# Regulation.net
KiCad netlist of a schematic drawn in Altium Designer
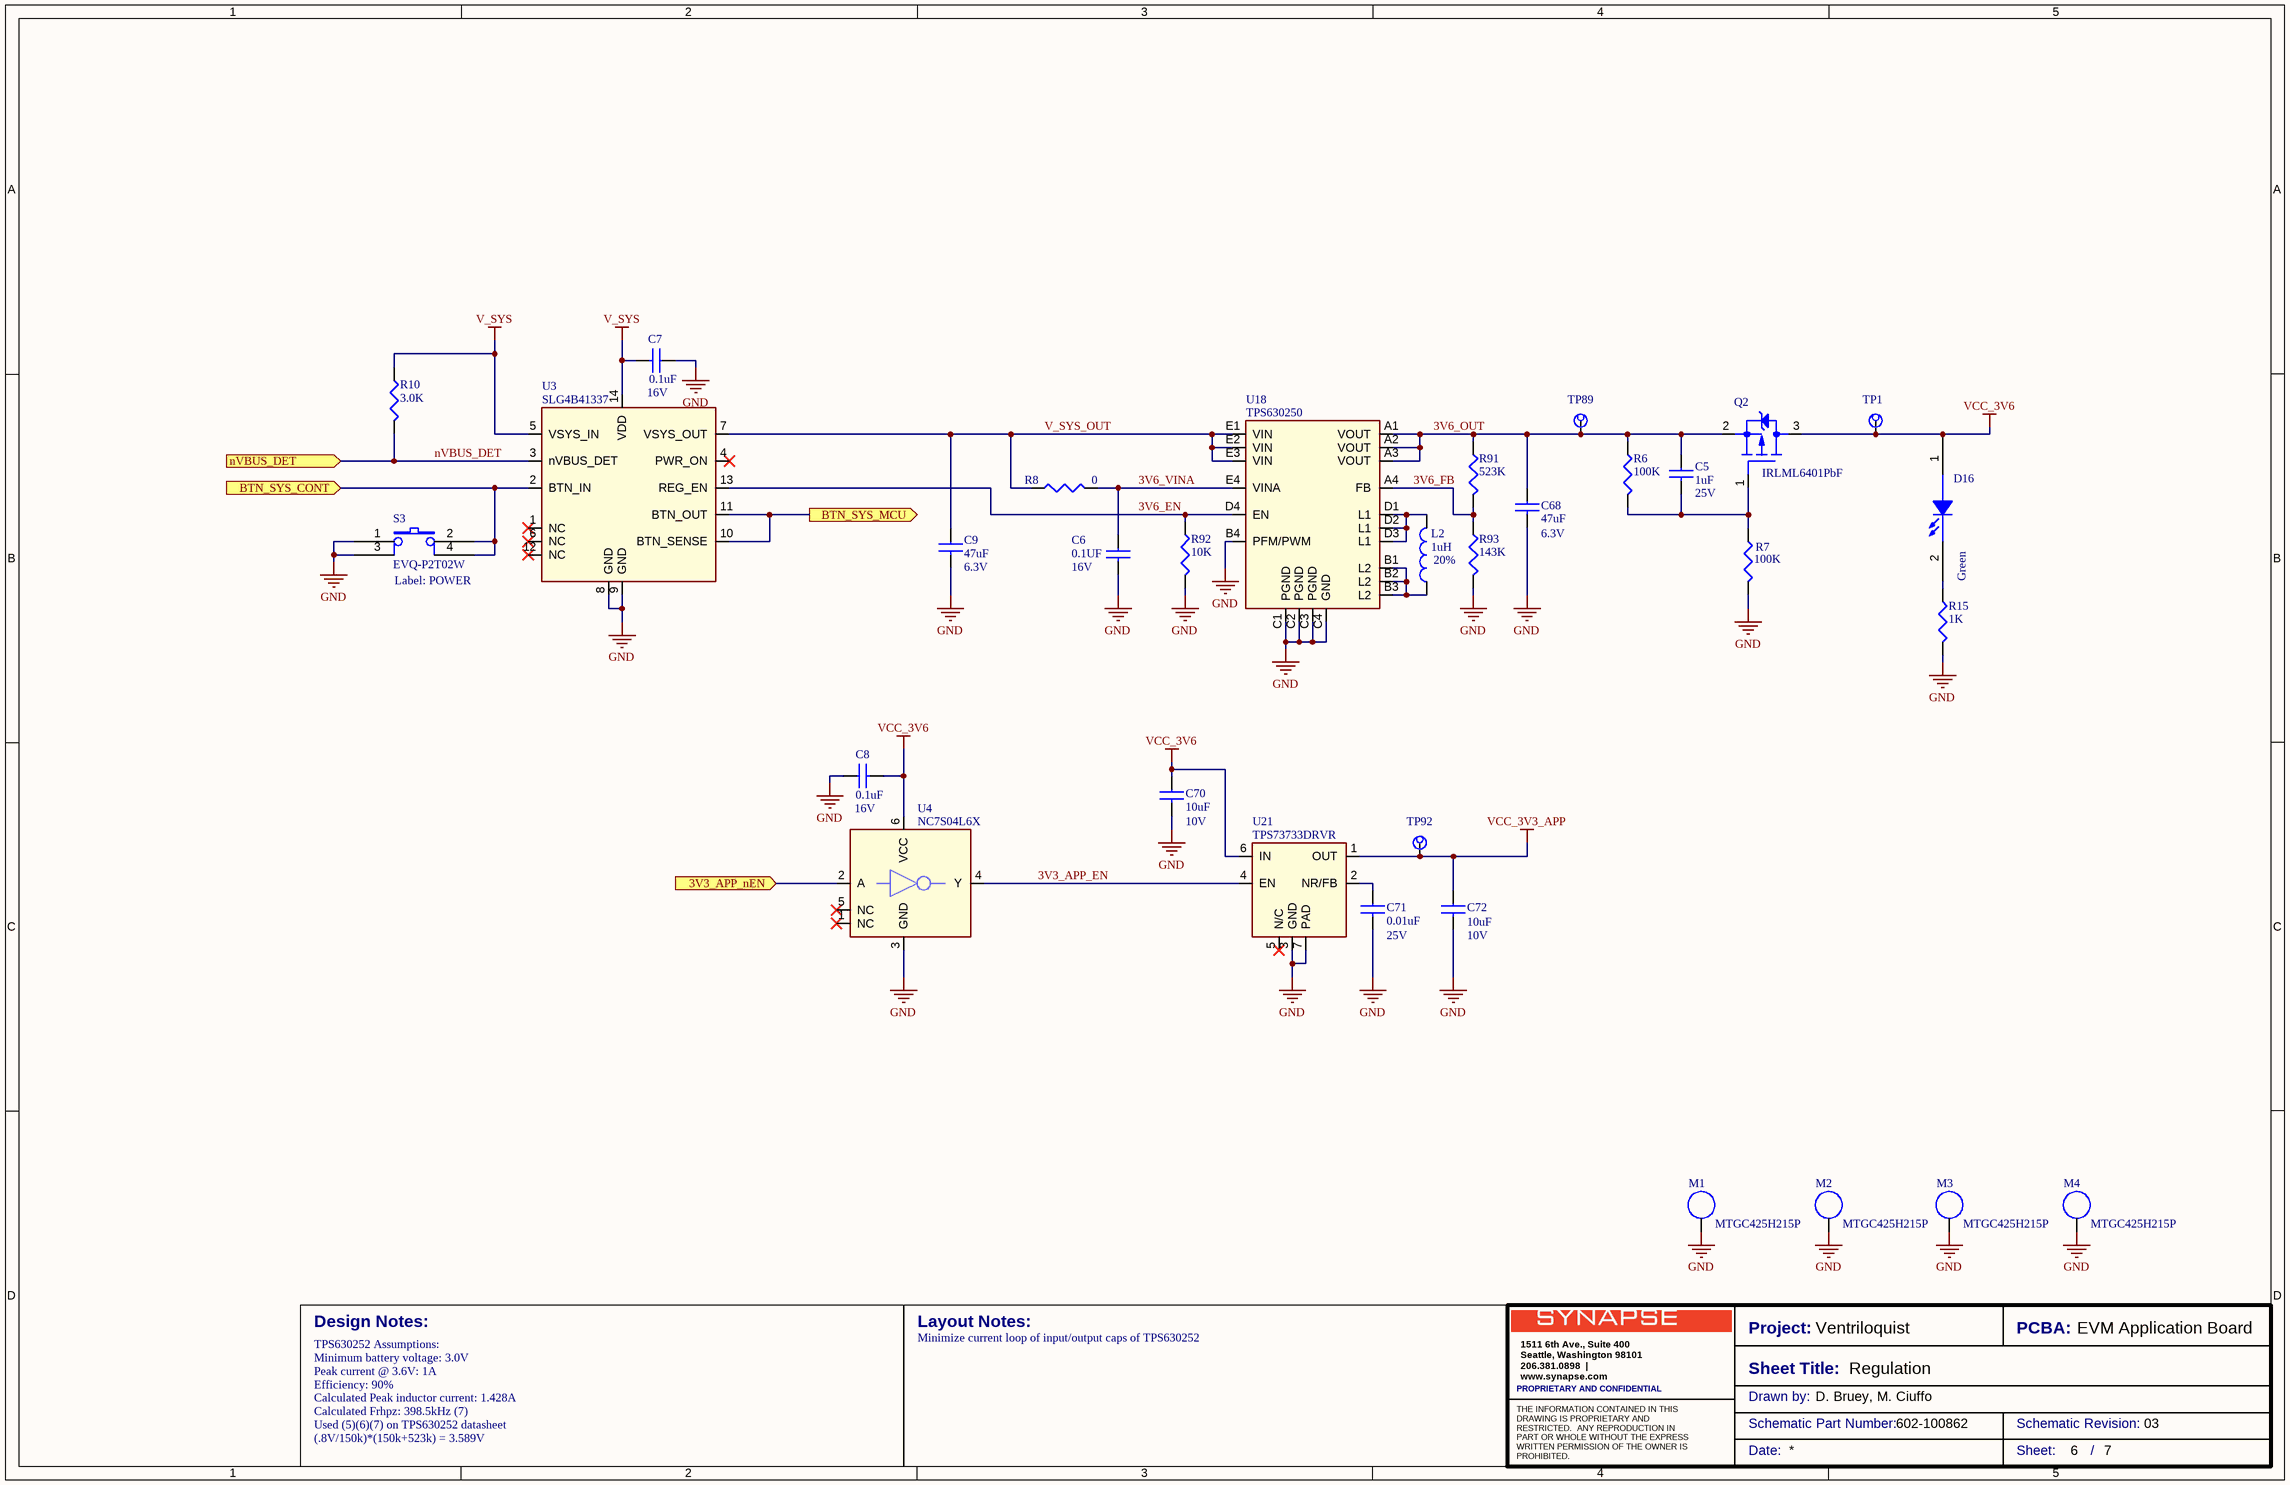
[diagram p0: Regulation.SchDoc]

(export (version "E")
  (design (tool "Eeschema 10.0.6"))
  (components
    (comp (ref "C5")
      (value "1uF")
      (footprint "0603-IPCsm_90")
      (description "CAP CER 1UF 25V 10% X5R 0603")
      (fields (field (name "VOLTAGE") "25V") (field (name "MFG") "Murata") (field (name "TOLERANCE") "10%"))
      (libsource (lib "SynapseLibrary") (part "CAP"))
    )
    (comp (ref "C6")
      (value "0.1UF")
      (footprint "0603-ipcsm_90")
      (description "CAP CER 0.1UF 16V 5% X7R 0603")
      (fields (field (name "VOLTAGE") "16V") (field (name "MFG") "Kemet") (field (name "TOLERANCE") "5%"))
      (libsource (lib "SynapseLibrary") (part "CAP"))
    )
    (comp (ref "C7")
      (value "0.1uF")
      (footprint "0402-IPCsm_55")
      (description "CAP CER .1UF 16V X7R 0402")
      (fields (field (name "VOLTAGE") "16V") (field (name "MFG") "MURATA") (field (name "TOLERANCE") "10%"))
      (libsource (lib "SynapseLibrary") (part "CAP"))
    )
    (comp (ref "C8")
      (value "0.1uF")
      (footprint "0402-IPCsm_55")
      (description "CAP CER .1UF 16V X7R 0402")
      (fields (field (name "VOLTAGE") "16V") (field (name "MFG") "MURATA") (field (name "TOLERANCE") "10%"))
      (libsource (lib "SynapseLibrary") (part "CAP"))
    )
    (comp (ref "C9")
      (value "47uF")
      (footprint "0805-ipcsm_145")
      (description "CAP CER 47UF 6.3V 20% X5R 0805")
      (fields (field (name "VOLTAGE") "6.3V") (field (name "MFG") "TDK") (field (name "TOLERANCE") "20%"))
      (libsource (lib "SynapseLibrary") (part "CAP"))
    )
    (comp (ref "C68")
      (value "47uF")
      (footprint "0805-ipcsm_145")
      (description "CAP CER 47UF 6.3V 20% X5R 0805")
      (fields (field (name "VOLTAGE") "6.3V") (field (name "MFG") "TDK") (field (name "TOLERANCE") "20%"))
      (libsource (lib "SynapseLibrary") (part "CAP"))
    )
    (comp (ref "C70")
      (value "10uF")
      (footprint "0603-IPCsm_90")
      (description "CAP CER 10UF 10V 10% X5R 0603")
      (fields (field (name "VOLTAGE") "10V") (field (name "MFG") "TDK") (field (name "TOLERANCE") "10%"))
      (libsource (lib "SynapseLibrary") (part "CAP"))
    )
    (comp (ref "C71")
      (value "0.01uF")
      (footprint "0402-IPCsm_55")
      (description "CAP, 0.01 uF, 25V, 10%, 0402, X7R")
      (fields (field (name "VOLTAGE") "25V") (field (name "MFG") "MURATA") (field (name "TOLERANCE") "10%"))
      (libsource (lib "SynapseLibrary") (part "CAP"))
    )
    (comp (ref "C72")
      (value "10uF")
      (footprint "0603-IPCsm_90")
      (description "CAP CER 10UF 10V 10% X5R 0603")
      (fields (field (name "VOLTAGE") "10V") (field (name "MFG") "TDK") (field (name "TOLERANCE") "10%"))
      (libsource (lib "SynapseLibrary") (part "CAP"))
    )
    (comp (ref "D16")
      (value "Green")
      (footprint "led_ltst-c191kgkt_s80")
      (description "LED GREEN CLEAR THIN 0603 SMD")
      (fields (field (name "MFG") "Lite-On Inc") (field (name "VOLTAGE") "3.2V"))
      (libsource (lib "SynapseLibrary") (part "LED"))
    )
    (comp (ref "L2")
      (value "1uH")
      (footprint "ind-1008_35H")
      (description "INDUCTOR 1.0UH 20% 1600MA 1008")
      (fields (field (name "TOLERANCE") "20%") (field (name "MFG") "MURATA"))
      (libsource (lib "SynapseLibrary") (part "IND_H"))
    )
    (comp (ref "M1")
      (value "MTGC425H215P")
      (footprint "MTGC425H215P")
      (description "MTG, 4.25mm PAD, 2.15mm Plated Hole")
      (libsource (lib "SynapseLibrary") (part "MTG"))
    )
    (comp (ref "M2")
      (value "MTGC425H215P")
      (footprint "MTGC425H215P")
      (description "MTG, 4.25mm PAD, 2.15mm Plated Hole")
      (libsource (lib "SynapseLibrary") (part "MTG"))
    )
    (comp (ref "M3")
      (value "MTGC425H215P")
      (footprint "MTGC425H215P")
      (description "MTG, 4.25mm PAD, 2.15mm Plated Hole")
      (libsource (lib "SynapseLibrary") (part "MTG"))
    )
    (comp (ref "M4")
      (value "MTGC425H215P")
      (footprint "MTGC425H215P")
      (description "MTG, 4.25mm PAD, 2.15mm Plated Hole")
      (libsource (lib "SynapseLibrary") (part "MTG"))
    )
    (comp (ref "Q2")
      (value "IRLML6401PbF")
      (footprint "SOT23_112")
      (description "MOSFET P-CH 12V 4.3A SOT-23")
      (fields (field (name "MFG") "International Rectifier"))
      (libsource (lib "SynapseLibrary") (part "IRLML6401PbF"))
    )
    (comp (ref "R6")
      (value "100K")
      (footprint "0402-IPCsm_40")
      (description "RES 100K OHM 1/16W 5% 0402 SMD")
      (fields (field (name "TOLERANCE") "5.00%") (field (name "MFG") "PANASONIC"))
      (libsource (lib "SynapseLibrary") (part "RES"))
    )
    (comp (ref "R7")
      (value "100K")
      (footprint "0402-IPCsm_40")
      (description "RES 100K OHM 1/16W 5% 0402 SMD")
      (fields (field (name "TOLERANCE") "5.00%") (field (name "MFG") "PANASONIC"))
      (libsource (lib "SynapseLibrary") (part "RES"))
    )
    (comp (ref "R8")
      (value "0")
      (footprint "0402-IPCsm_40")
      (description "RES 0.0 OHM 1/10W JUMP 0402 SMD")
      (fields (field (name "TOLERANCE") "5.00%") (field (name "MFG") "PANASONIC"))
      (libsource (lib "SynapseLibrary") (part "RES"))
    )
    (comp (ref "R10")
      (value "3.0K")
      (footprint "0402-IPCsm_40")
      (description "RES 3.00K OHM 1/16W 1% 0402 SMD")
      (fields (field (name "TOLERANCE") "1.00%") (field (name "VOLTAGE") "50V"))
      (libsource (lib "SynapseLibrary") (part "RES"))
    )
    (comp (ref "R15")
      (value "1K")
      (footprint "0603-IPCsm_56")
      (description "RES 1K 1/10W 1% 0603 SMD")
      (fields (field (name "TOLERANCE") "1.00%") (field (name "VOLTAGE") "50V"))
      (libsource (lib "SynapseLibrary") (part "RES"))
    )
    (comp (ref "R91")
      (value "523K")
      (footprint "0402-IPCsm_40")
      (description "RES SMD 523K OHM 1% 1/10W 0402")
      (fields (field (name "TOLERANCE") "0.1%") (field (name "MFG") "PANASONIC"))
      (libsource (lib "SynapseLibrary") (part "RES"))
    )
    (comp (ref "R92")
      (value "10K")
      (footprint "0402-IPCsm_40")
      (description "RES 10K OHM 1/10W 5% 0402 SMD")
      (fields (field (name "TOLERANCE") "5%") (field (name "MFG") "Panasonic"))
      (libsource (lib "SynapseLibrary") (part "RES"))
    )
    (comp (ref "R93")
      (value "143K")
      (footprint "0402-IPCsm_40")
      (description "RES 143K OHM 1/16W 1% 0402 SMD")
      (fields (field (name "TOLERANCE") "1.00%") (field (name "VOLTAGE") "50V"))
      (libsource (lib "SynapseLibrary") (part "RES"))
    )
    (comp (ref "S3")
      (value "EVQ-P2T02W")
      (footprint "SW_EVQP2")
      (description "SWITCH TACTILE SPST-NO 0.02A 15V")
      (fields (field (name "MFG") "Panasonic") (field (name "VOLTAGE") "15VDC"))
      (libsource (lib "SynapseLibrary") (part "EVQ-P2T02W"))
    )
    (comp (ref "TP1")
      (value "TPC150H080P")
      (footprint "TPC150H080P")
      (description "TESTPOINT, 1.5mm pad, 0.8 mm plated")
      (fields (field (name "MFG") "NA"))
      (libsource (lib "SynapseLibrary") (part "tp_th"))
    )
    (comp (ref "TP89")
      (value "TPC150H080P")
      (footprint "TPC150H080P")
      (description "TESTPOINT, 1.5mm pad, 0.8 mm plated")
      (fields (field (name "MFG") "NA"))
      (libsource (lib "SynapseLibrary") (part "tp_th"))
    )
    (comp (ref "TP92")
      (value "TPC150H080P")
      (footprint "TPC150H080P")
      (description "TESTPOINT, 1.5mm pad, 0.8 mm plated")
      (fields (field (name "MFG") "NA"))
      (libsource (lib "SynapseLibrary") (part "tp_th"))
    )
    (comp (ref "U3")
      (value "SLG4B41337")
      (footprint "stqfn14_250x160x60")
      (description "GreenPAK Programmable Mixed Signal Array 14 pin")
      (fields (field (name "MFG") "Silego"))
      (libsource (lib "SynapseLibrary") (part "SLG46116V_VENT"))
    )
    (comp (ref "U4")
      (value "NC7S04L6X")
      (footprint "DFN6-NC7S04_110H")
      (description "Inverter IC 1 Channel 6-MicroPak")
      (fields (field (name "MFG") "Fairchild") (field (name "VOLTAGE") "2V-6V"))
      (libsource (lib "SynapseLibrary") (part "NC7S04L6X"))
    )
    (comp (ref "U18")
      (value "TPS630250")
      (footprint "bga20_tps630252-YFF")
      (description "IC REG BCK BST ADJ 2A/4A 20DSBGA")
      (fields (field (name "MFG") "TI") (field (name "VOLTAGE") "2.3V~5.5V"))
      (libsource (lib "SynapseLibrary") (part "TPS63025X"))
    )
    (comp (ref "U21")
      (value "TPS73733DRVR")
      (footprint "SON6_TPS73733DRV")
      (description "IC REG LDO 3.3V 1A 6SON")
      (fields (field (name "MFG") "TI") (field (name "VOLTAGE") "2.2V~5.5V"))
      (libsource (lib "SynapseLibrary") (part "TPS737xx"))
    )
  )
  (nets
    (net (code "1") (name "/3V3_APP_EN") (class "Default")
      (node (ref "U21") (pin "4") (pinfunction "EN_4") (pintype "passive"))
      (node (ref "U4") (pin "4") (pinfunction "Y_4") (pintype "passive"))
    )
    (net (code "2") (name "/3V3_APP_nEN") (class "Default")
      (node (ref "U4") (pin "2") (pinfunction "A_2") (pintype "passive"))
    )
    (net (code "3") (name "/3V6_EN") (class "Default")
      (node (ref "R92") (pin "1") (pinfunction "1_1") (pintype "passive"))
      (node (ref "U18") (pin "D4") (pinfunction "EN_D4") (pintype "passive"))
      (node (ref "U3") (pin "13") (pinfunction "REG_EN_13") (pintype "passive"))
    )
    (net (code "4") (name "/3V6_FB") (class "Default")
      (node (ref "R91") (pin "2") (pinfunction "2_2") (pintype "passive"))
      (node (ref "R93") (pin "1") (pinfunction "1_1") (pintype "passive"))
      (node (ref "U18") (pin "A4") (pinfunction "FB_A4") (pintype "passive"))
    )
    (net (code "5") (name "/3V6_OUT") (class "Default")
      (node (ref "C5") (pin "1") (pinfunction "1_1") (pintype "passive"))
      (node (ref "C68") (pin "1") (pinfunction "1_1") (pintype "passive"))
      (node (ref "Q2") (pin "2") (pinfunction "S_2") (pintype "passive"))
      (node (ref "R6") (pin "1") (pinfunction "1_1") (pintype "passive"))
      (node (ref "R91") (pin "1") (pinfunction "1_1") (pintype "passive"))
      (node (ref "TP89") (pin "1") (pinfunction "TP_1") (pintype "passive"))
      (node (ref "U18") (pin "A1") (pinfunction "VOUT_A1") (pintype "passive"))
      (node (ref "U18") (pin "A2") (pinfunction "VOUT_A2") (pintype "passive"))
      (node (ref "U18") (pin "A3") (pinfunction "VOUT_A3") (pintype "passive"))
    )
    (net (code "6") (name "/3V6_VINA") (class "Default")
      (node (ref "C6") (pin "1") (pinfunction "1_1") (pintype "passive"))
      (node (ref "R8") (pin "2") (pinfunction "2_2") (pintype "passive"))
      (node (ref "U18") (pin "E4") (pinfunction "VINA_E4") (pintype "passive"))
    )
    (net (code "7") (name "/BTN_SYS_CONT") (class "Default")
      (node (ref "S3") (pin "2") (pinfunction "2_2") (pintype "passive"))
      (node (ref "S3") (pin "4") (pinfunction "4_4") (pintype "passive"))
      (node (ref "U3") (pin "2") (pinfunction "BTN_IN_2") (pintype "passive"))
    )
    (net (code "8") (name "/BTN_SYS_MCU") (class "Default")
      (node (ref "U3") (pin "10") (pinfunction "BTN_SENSE_10") (pintype "passive"))
      (node (ref "U3") (pin "11") (pinfunction "BTN_OUT_11") (pintype "passive"))
    )
    (net (code "9") (name "/V_SYS_OUT") (class "Default")
      (node (ref "C9") (pin "1") (pinfunction "1_1") (pintype "passive"))
      (node (ref "R8") (pin "1") (pinfunction "1_1") (pintype "passive"))
      (node (ref "U18") (pin "E1") (pinfunction "VIN_E1") (pintype "passive"))
      (node (ref "U18") (pin "E2") (pinfunction "VIN_E2") (pintype "passive"))
      (node (ref "U18") (pin "E3") (pinfunction "VIN_E3") (pintype "passive"))
      (node (ref "U3") (pin "7") (pinfunction "VSYS_OUT_7") (pintype "passive"))
    )
    (net (code "10") (name "/nVBUS_DET") (class "Default")
      (node (ref "R10") (pin "2") (pinfunction "2_2") (pintype "passive"))
      (node (ref "U3") (pin "3") (pinfunction "nVBUS_DET_3") (pintype "passive"))
    )
    (net (code "11") (name "GND") (class "Default")
      (node (ref "C6") (pin "2") (pinfunction "2_2") (pintype "passive"))
      (node (ref "C68") (pin "2") (pinfunction "2_2") (pintype "passive"))
      (node (ref "C7") (pin "1") (pinfunction "1_1") (pintype "passive"))
      (node (ref "C70") (pin "2") (pinfunction "2_2") (pintype "passive"))
      (node (ref "C71") (pin "2") (pinfunction "2_2") (pintype "passive"))
      (node (ref "C72") (pin "2") (pinfunction "2_2") (pintype "passive"))
      (node (ref "C8") (pin "1") (pinfunction "1_1") (pintype "passive"))
      (node (ref "C9") (pin "2") (pinfunction "2_2") (pintype "passive"))
      (node (ref "M1") (pin "1") (pinfunction "1_1") (pintype "passive"))
      (node (ref "M2") (pin "1") (pinfunction "1_1") (pintype "passive"))
      (node (ref "M3") (pin "1") (pinfunction "1_1") (pintype "passive"))
      (node (ref "M4") (pin "1") (pinfunction "1_1") (pintype "passive"))
      (node (ref "R15") (pin "2") (pinfunction "2_2") (pintype "passive"))
      (node (ref "R7") (pin "2") (pinfunction "2_2") (pintype "passive"))
      (node (ref "R92") (pin "2") (pinfunction "2_2") (pintype "passive"))
      (node (ref "R93") (pin "2") (pinfunction "2_2") (pintype "passive"))
      (node (ref "S3") (pin "1") (pinfunction "1_1") (pintype "passive"))
      (node (ref "S3") (pin "3") (pinfunction "3_3") (pintype "passive"))
      (node (ref "U18") (pin "B4") (pinfunction "PFM/PWM_B4") (pintype "passive"))
      (node (ref "U18") (pin "C1") (pinfunction "PGND_C1") (pintype "passive"))
      (node (ref "U18") (pin "C2") (pinfunction "PGND_C2") (pintype "passive"))
      (node (ref "U18") (pin "C3") (pinfunction "PGND_C3") (pintype "passive"))
      (node (ref "U18") (pin "C4") (pinfunction "GND_C4") (pintype "passive"))
      (node (ref "U21") (pin "3") (pinfunction "GND_3") (pintype "passive"))
      (node (ref "U21") (pin "7") (pinfunction "PAD_7") (pintype "passive"))
      (node (ref "U3") (pin "8") (pinfunction "GND_8") (pintype "passive"))
      (node (ref "U3") (pin "9") (pinfunction "GND_9") (pintype "passive"))
      (node (ref "U4") (pin "3") (pinfunction "GND_3") (pintype "passive"))
    )
    (net (code "12") (name "Net-(D16-C)") (class "Default")
      (node (ref "D16") (pin "2") (pinfunction "C_2") (pintype "passive"))
      (node (ref "R15") (pin "1") (pinfunction "1_1") (pintype "passive"))
    )
    (net (code "13") (name "Net-(L2-Pad1)") (class "Default")
      (node (ref "L2") (pin "1") (pinfunction "1_1") (pintype "passive"))
      (node (ref "U18") (pin "B1") (pinfunction "L2_B1") (pintype "passive"))
      (node (ref "U18") (pin "B2") (pinfunction "L2_B2") (pintype "passive"))
      (node (ref "U18") (pin "B3") (pinfunction "L2_B3") (pintype "passive"))
    )
    (net (code "14") (name "Net-(L2-Pad2)") (class "Default")
      (node (ref "L2") (pin "2") (pinfunction "2_2") (pintype "passive"))
      (node (ref "U18") (pin "D1") (pinfunction "L1_D1") (pintype "passive"))
      (node (ref "U18") (pin "D2") (pinfunction "L1_D2") (pintype "passive"))
      (node (ref "U18") (pin "D3") (pinfunction "L1_D3") (pintype "passive"))
    )
    (net (code "15") (name "Net-(Q2-G)") (class "Default")
      (node (ref "C5") (pin "2") (pinfunction "2_2") (pintype "passive"))
      (node (ref "Q2") (pin "1") (pinfunction "G_1") (pintype "passive"))
      (node (ref "R6") (pin "2") (pinfunction "2_2") (pintype "passive"))
      (node (ref "R7") (pin "1") (pinfunction "1_1") (pintype "passive"))
    )
    (net (code "16") (name "Net-(U21-NR{slash}FB)") (class "Default")
      (node (ref "C71") (pin "1") (pinfunction "1_1") (pintype "passive"))
      (node (ref "U21") (pin "2") (pinfunction "NR/FB_2") (pintype "passive"))
    )
    (net (code "17") (name "VCC_3V3_APP") (class "Default")
      (node (ref "C72") (pin "1") (pinfunction "1_1") (pintype "passive"))
      (node (ref "TP92") (pin "1") (pinfunction "TP_1") (pintype "passive"))
      (node (ref "U21") (pin "1") (pinfunction "OUT_1") (pintype "passive"))
    )
    (net (code "18") (name "VCC_3V6") (class "Default")
      (node (ref "C70") (pin "1") (pinfunction "1_1") (pintype "passive"))
      (node (ref "C8") (pin "2") (pinfunction "2_2") (pintype "passive"))
      (node (ref "D16") (pin "1") (pinfunction "A_1") (pintype "passive"))
      (node (ref "Q2") (pin "3") (pinfunction "D_3") (pintype "passive"))
      (node (ref "TP1") (pin "1") (pinfunction "TP_1") (pintype "passive"))
      (node (ref "U21") (pin "6") (pinfunction "IN_6") (pintype "passive"))
      (node (ref "U4") (pin "6") (pinfunction "VCC_6") (pintype "passive"))
    )
    (net (code "19") (name "V_SYS") (class "Default")
      (node (ref "C7") (pin "2") (pinfunction "2_2") (pintype "passive"))
      (node (ref "R10") (pin "1") (pinfunction "1_1") (pintype "passive"))
      (node (ref "U3") (pin "14") (pinfunction "VDD_14") (pintype "passive"))
      (node (ref "U3") (pin "5") (pinfunction "VSYS_IN_5") (pintype "passive"))
    )
    (net (code "20") (name "unconnected-(U3-NC-Pad1)") (class "Default")
      (node (ref "U3") (pin "1") (pinfunction "NC_1") (pintype "passive+no_connect"))
    )
    (net (code "21") (name "unconnected-(U3-NC-Pad6)") (class "Default")
      (node (ref "U3") (pin "6") (pinfunction "NC_6") (pintype "passive+no_connect"))
    )
    (net (code "22") (name "unconnected-(U3-NC-Pad12)") (class "Default")
      (node (ref "U3") (pin "12") (pinfunction "NC_12") (pintype "passive+no_connect"))
    )
    (net (code "23") (name "unconnected-(U3-PWR_ON-Pad4)") (class "Default")
      (node (ref "U3") (pin "4") (pinfunction "PWR_ON_4") (pintype "passive+no_connect"))
    )
    (net (code "24") (name "unconnected-(U4-NC-Pad1)") (class "Default")
      (node (ref "U4") (pin "1") (pinfunction "NC_1") (pintype "passive+no_connect"))
    )
    (net (code "25") (name "unconnected-(U4-NC-Pad5)") (class "Default")
      (node (ref "U4") (pin "5") (pinfunction "NC_5") (pintype "passive+no_connect"))
    )
    (net (code "26") (name "unconnected-(U21-N{slash}C-Pad5)") (class "Default")
      (node (ref "U21") (pin "5") (pinfunction "N/C_5") (pintype "passive+no_connect"))
    )
  )
)
